# example-mcp23017-circuit.net
KiCad netlist of a schematic drawn in EAGLE
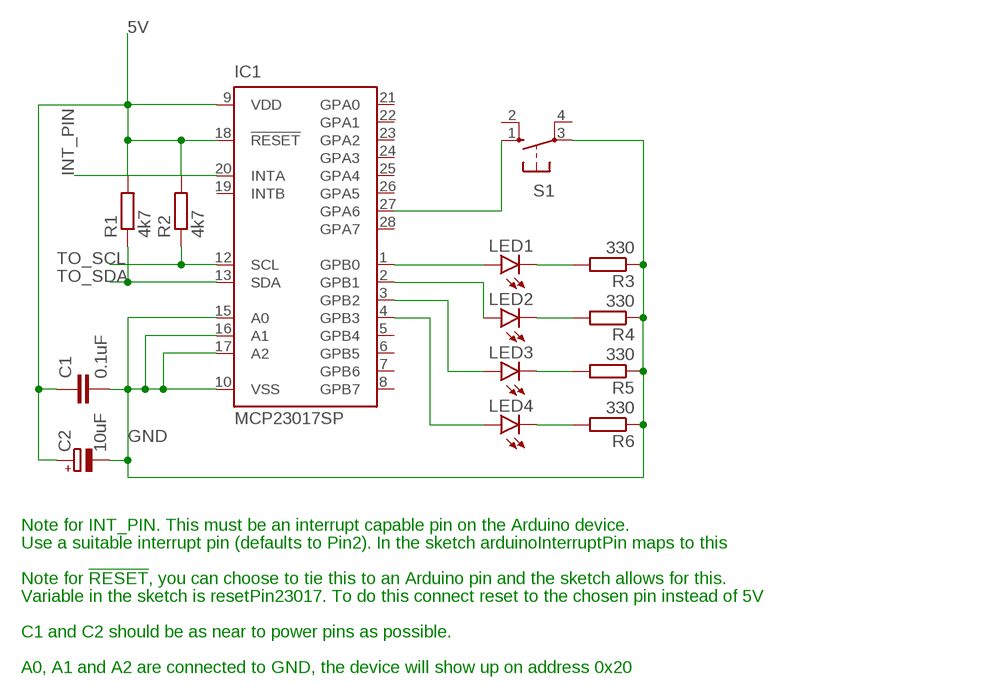
[diagram p0: schematic, sheet 1]

(export (version "E")
  (design (tool "Eeschema 10.0.6"))
  (components
    (comp (ref "C1")
      (value "0.1uF")
      (footprint "eagle-import:C025-025X050")
      (libsource (lib "eagle-import") (part "C-EU025-025X050"))
    )
    (comp (ref "C2")
      (value "10uF")
      (footprint "eagle-import:E1,8-4")
      (libsource (lib "eagle-import") (part "CPOL-EUE1.8-4"))
    )
    (comp (ref "IC1")
      (value "MCP23017SP")
      (footprint "eagle-import:DIL28-3")
      (libsource (lib "eagle-import") (part "MCP23017SP"))
    )
    (comp (ref "LED1")
      (value "LED5MM")
      (footprint "eagle-import:LED5MM")
      (libsource (lib "eagle-import") (part "LED5MM"))
    )
    (comp (ref "LED2")
      (value "LED5MM")
      (footprint "eagle-import:LED5MM")
      (libsource (lib "eagle-import") (part "LED5MM"))
    )
    (comp (ref "LED3")
      (value "LED5MM")
      (footprint "eagle-import:LED5MM")
      (libsource (lib "eagle-import") (part "LED5MM"))
    )
    (comp (ref "LED4")
      (value "LED5MM")
      (footprint "eagle-import:LED5MM")
      (libsource (lib "eagle-import") (part "LED5MM"))
    )
    (comp (ref "R1")
      (value "4k7")
      (footprint "eagle-import:0204_7")
      (libsource (lib "eagle-import") (part "R-EU_0204/7"))
    )
    (comp (ref "R2")
      (value "4k7")
      (footprint "eagle-import:0204_7")
      (libsource (lib "eagle-import") (part "R-EU_0204/7"))
    )
    (comp (ref "R3")
      (value "330")
      (footprint "eagle-import:0204_7")
      (libsource (lib "eagle-import") (part "R-EU_0204/7"))
    )
    (comp (ref "R4")
      (value "330")
      (footprint "eagle-import:0204_7")
      (libsource (lib "eagle-import") (part "R-EU_0204/7"))
    )
    (comp (ref "R5")
      (value "330")
      (footprint "eagle-import:0204_7")
      (libsource (lib "eagle-import") (part "R-EU_0204/7"))
    )
    (comp (ref "R6")
      (value "330")
      (footprint "eagle-import:0204_7")
      (libsource (lib "eagle-import") (part "R-EU_0204/7"))
    )
    (comp (ref "S1")
      (value "10-XX")
      (footprint "eagle-import:B3F-10XX")
      (fields (field (name "MPN") "B3F-1000"))
      (libsource (lib "eagle-import") (part "10-XX"))
    )
  )
  (nets
    (net (code "1") (name "/5V") (class "Default")
      (node (ref "C1") (pin "1") (pinfunction "1_1") (pintype "passive"))
      (node (ref "C2") (pin "+") (pinfunction "+_+") (pintype "passive"))
      (node (ref "IC1") (pin "18") (pinfunction "~{RESET}_18") (pintype "input"))
      (node (ref "IC1") (pin "9") (pinfunction "VDD_9") (pintype "power_in"))
      (node (ref "R1") (pin "2") (pinfunction "2_2") (pintype "passive"))
      (node (ref "R2") (pin "2") (pinfunction "2_2") (pintype "passive"))
    )
    (net (code "2") (name "/GND") (class "Default")
      (node (ref "C1") (pin "2") (pinfunction "2_2") (pintype "passive"))
      (node (ref "C2") (pin "-") (pinfunction "-_-") (pintype "passive"))
      (node (ref "IC1") (pin "10") (pinfunction "VSS_10") (pintype "power_in"))
      (node (ref "IC1") (pin "15") (pinfunction "A0_15") (pintype "input"))
      (node (ref "IC1") (pin "16") (pinfunction "A1_16") (pintype "input"))
      (node (ref "IC1") (pin "17") (pinfunction "A2_17") (pintype "input"))
      (node (ref "R3") (pin "1") (pinfunction "1_1") (pintype "passive"))
      (node (ref "R4") (pin "1") (pinfunction "1_1") (pintype "passive"))
      (node (ref "R5") (pin "1") (pinfunction "1_1") (pintype "passive"))
      (node (ref "R6") (pin "1") (pinfunction "1_1") (pintype "passive"))
      (node (ref "S1") (pin "3") (pinfunction "P_3") (pintype "passive"))
    )
    (net (code "3") (name "/INT_PIN") (class "Default")
      (node (ref "IC1") (pin "20") (pinfunction "INTA_20") (pintype "output"))
    )
    (net (code "4") (name "/TO_SCL") (class "Default")
      (node (ref "IC1") (pin "12") (pinfunction "SCL_12") (pintype "input"))
      (node (ref "R2") (pin "1") (pinfunction "1_1") (pintype "passive"))
    )
    (net (code "5") (name "/TO_SDA") (class "Default")
      (node (ref "IC1") (pin "13") (pinfunction "SDA_13") (pintype "bidirectional"))
      (node (ref "R1") (pin "1") (pinfunction "1_1") (pintype "passive"))
    )
    (net (code "6") (name "Net-(IC1-GPA6)") (class "Default")
      (node (ref "IC1") (pin "27") (pinfunction "GPA6_27") (pintype "bidirectional"))
      (node (ref "S1") (pin "1") (pinfunction "S_1") (pintype "passive"))
    )
    (net (code "7") (name "Net-(IC1-GPB0)") (class "Default")
      (node (ref "IC1") (pin "1") (pinfunction "GPB0_1") (pintype "bidirectional"))
      (node (ref "LED1") (pin "A") (pinfunction "A_A") (pintype "passive"))
    )
    (net (code "8") (name "Net-(IC1-GPB1)") (class "Default")
      (node (ref "IC1") (pin "2") (pinfunction "GPB1_2") (pintype "bidirectional"))
      (node (ref "LED2") (pin "A") (pinfunction "A_A") (pintype "passive"))
    )
    (net (code "9") (name "Net-(IC1-GPB2)") (class "Default")
      (node (ref "IC1") (pin "3") (pinfunction "GPB2_3") (pintype "bidirectional"))
      (node (ref "LED3") (pin "A") (pinfunction "A_A") (pintype "passive"))
    )
    (net (code "10") (name "Net-(IC1-GPB3)") (class "Default")
      (node (ref "IC1") (pin "4") (pinfunction "GPB3_4") (pintype "bidirectional"))
      (node (ref "LED4") (pin "A") (pinfunction "A_A") (pintype "passive"))
    )
    (net (code "11") (name "Net-(LED1-C)") (class "Default")
      (node (ref "LED1") (pin "K") (pinfunction "C_K") (pintype "passive"))
      (node (ref "R3") (pin "2") (pinfunction "2_2") (pintype "passive"))
    )
    (net (code "12") (name "Net-(LED2-C)") (class "Default")
      (node (ref "LED2") (pin "K") (pinfunction "C_K") (pintype "passive"))
      (node (ref "R4") (pin "2") (pinfunction "2_2") (pintype "passive"))
    )
    (net (code "13") (name "Net-(LED3-C)") (class "Default")
      (node (ref "LED3") (pin "K") (pinfunction "C_K") (pintype "passive"))
      (node (ref "R5") (pin "2") (pinfunction "2_2") (pintype "passive"))
    )
    (net (code "14") (name "Net-(LED4-C)") (class "Default")
      (node (ref "LED4") (pin "K") (pinfunction "C_K") (pintype "passive"))
      (node (ref "R6") (pin "2") (pinfunction "2_2") (pintype "passive"))
    )
    (net (code "15") (name "unconnected-(IC1-GPA0-Pad21)") (class "Default")
      (node (ref "IC1") (pin "21") (pinfunction "GPA0_21") (pintype "bidirectional"))
    )
    (net (code "16") (name "unconnected-(IC1-GPA1-Pad22)") (class "Default")
      (node (ref "IC1") (pin "22") (pinfunction "GPA1_22") (pintype "bidirectional"))
    )
    (net (code "17") (name "unconnected-(IC1-GPA2-Pad23)") (class "Default")
      (node (ref "IC1") (pin "23") (pinfunction "GPA2_23") (pintype "bidirectional"))
    )
    (net (code "18") (name "unconnected-(IC1-GPA3-Pad24)") (class "Default")
      (node (ref "IC1") (pin "24") (pinfunction "GPA3_24") (pintype "bidirectional"))
    )
    (net (code "19") (name "unconnected-(IC1-GPA4-Pad25)") (class "Default")
      (node (ref "IC1") (pin "25") (pinfunction "GPA4_25") (pintype "bidirectional"))
    )
    (net (code "20") (name "unconnected-(IC1-GPA5-Pad26)") (class "Default")
      (node (ref "IC1") (pin "26") (pinfunction "GPA5_26") (pintype "bidirectional"))
    )
    (net (code "21") (name "unconnected-(IC1-GPA7-Pad28)") (class "Default")
      (node (ref "IC1") (pin "28") (pinfunction "GPA7_28") (pintype "bidirectional"))
    )
    (net (code "22") (name "unconnected-(IC1-GPB4-Pad5)") (class "Default")
      (node (ref "IC1") (pin "5") (pinfunction "GPB4_5") (pintype "bidirectional"))
    )
    (net (code "23") (name "unconnected-(IC1-GPB5-Pad6)") (class "Default")
      (node (ref "IC1") (pin "6") (pinfunction "GPB5_6") (pintype "bidirectional"))
    )
    (net (code "24") (name "unconnected-(IC1-GPB6-Pad7)") (class "Default")
      (node (ref "IC1") (pin "7") (pinfunction "GPB6_7") (pintype "bidirectional"))
    )
    (net (code "25") (name "unconnected-(IC1-GPB7-Pad8)") (class "Default")
      (node (ref "IC1") (pin "8") (pinfunction "GPB7_8") (pintype "bidirectional"))
    )
    (net (code "26") (name "unconnected-(IC1-INTB-Pad19)") (class "Default")
      (node (ref "IC1") (pin "19") (pinfunction "INTB_19") (pintype "output"))
    )
    (net (code "27") (name "unconnected-(S1-P1-Pad4)") (class "Default")
      (node (ref "S1") (pin "4") (pinfunction "P1_4") (pintype "passive"))
    )
    (net (code "28") (name "unconnected-(S1-S1-Pad2)") (class "Default")
      (node (ref "S1") (pin "2") (pinfunction "S1_2") (pintype "passive"))
    )
  )
)
